# Doorbell_With_Power_Supply.net
KiCad netlist of a schematic drawn in EAGLE
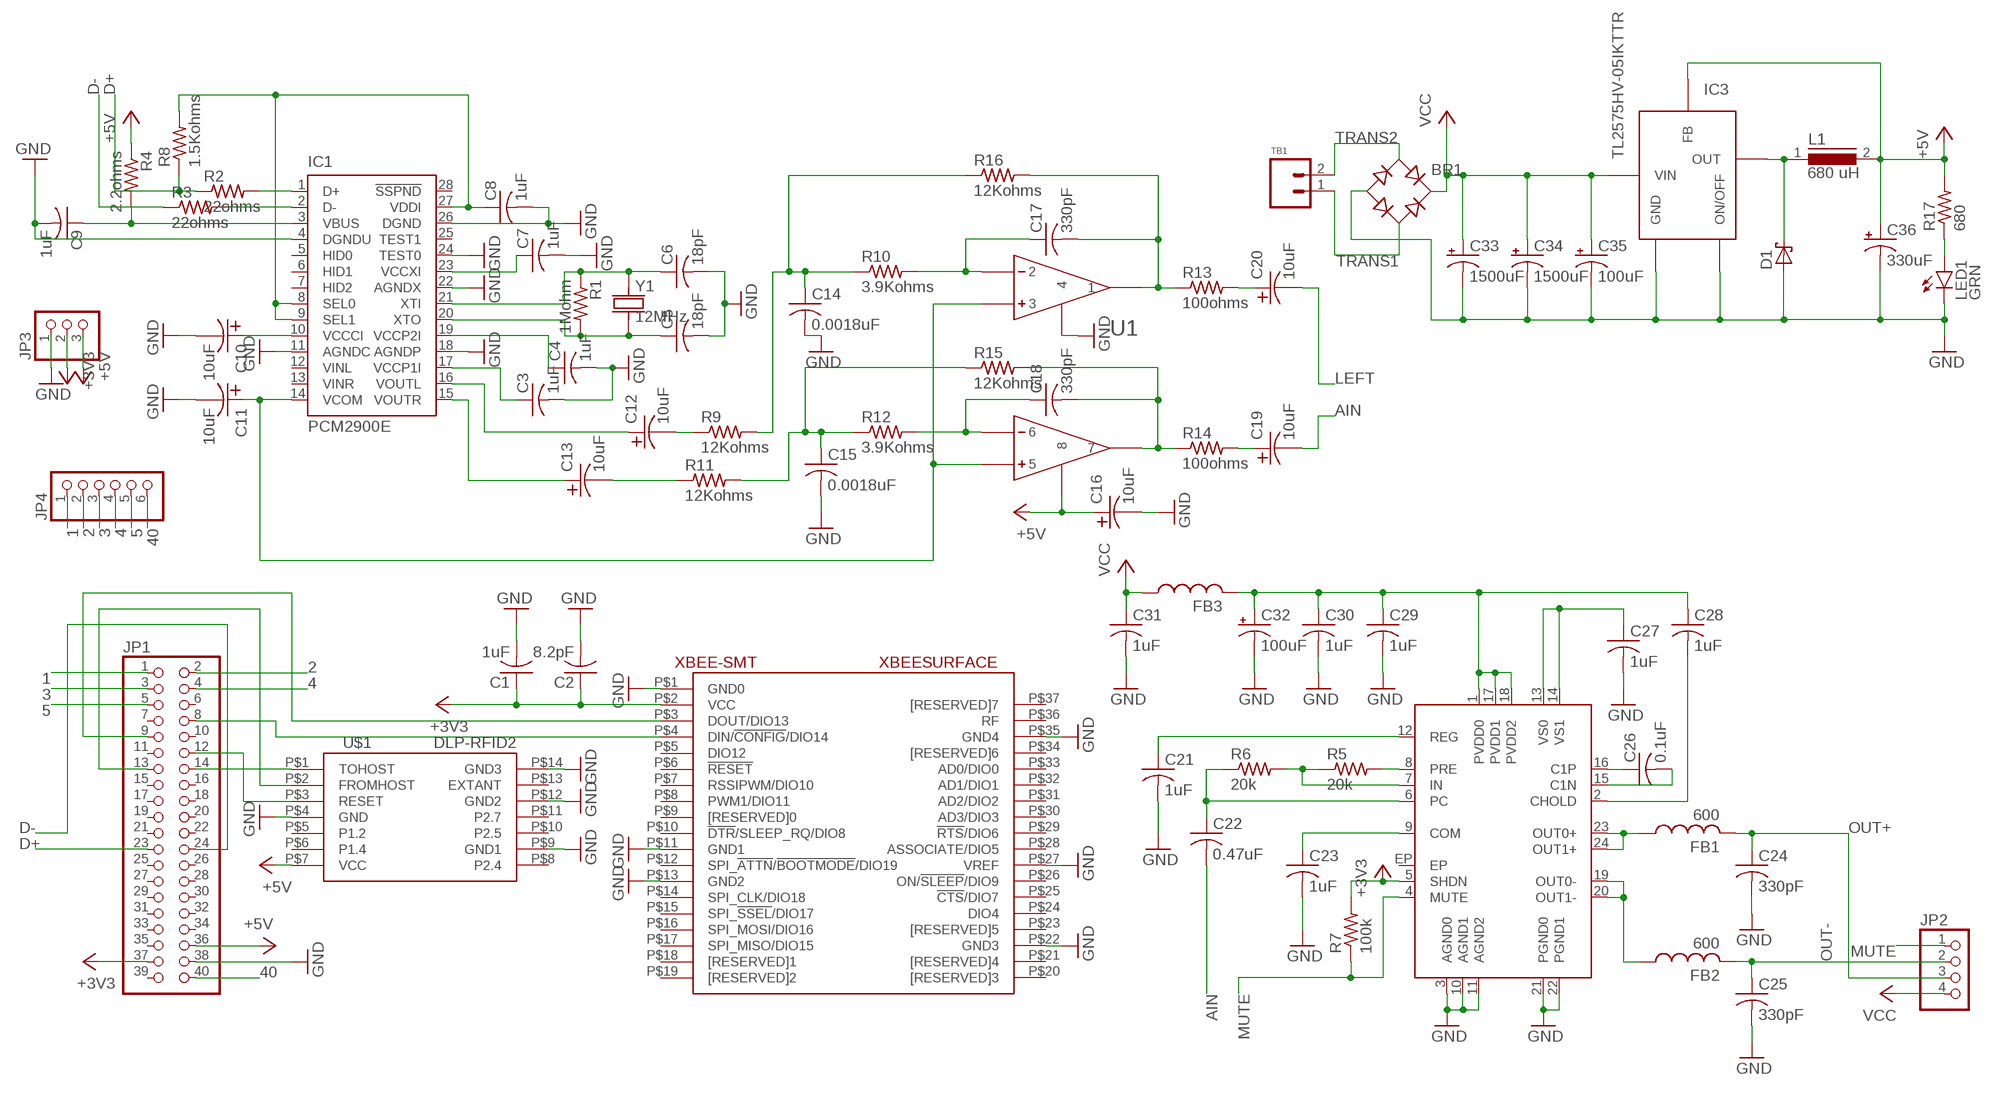
[diagram p0: schematic, sheet 1]

(export (version "E")
  (design (tool "Eeschema 10.0.6"))
  (components
    (comp (ref "BR1")
      (value "BR")
      (footprint "eagle-import:DFS")
      (fields (field (name "MANF") "Comchip Technology"))
      (libsource (lib "eagle-import") (part "BR"))
    )
    (comp (ref "C1")
      (value "1uF")
      (footprint "eagle-import:0603_CAP")
      (libsource (lib "eagle-import") (part "CAP0603"))
    )
    (comp (ref "C2")
      (value "8.2pF")
      (footprint "eagle-import:0603_CAP")
      (libsource (lib "eagle-import") (part "CAP0603"))
    )
    (comp (ref "C3")
      (value "1uF")
      (footprint "eagle-import:0603_CAP")
      (libsource (lib "eagle-import") (part "CAP0603"))
    )
    (comp (ref "C4")
      (value "1uF")
      (footprint "eagle-import:0603_CAP")
      (libsource (lib "eagle-import") (part "CAP0603"))
    )
    (comp (ref "C5")
      (value "18pF")
      (footprint "eagle-import:0603_CAP")
      (libsource (lib "eagle-import") (part "CAP0603"))
    )
    (comp (ref "C6")
      (value "18pF")
      (footprint "eagle-import:0603_CAP")
      (libsource (lib "eagle-import") (part "CAP0603"))
    )
    (comp (ref "C7")
      (value "1uF")
      (footprint "eagle-import:0603_CAP")
      (libsource (lib "eagle-import") (part "CAP0603"))
    )
    (comp (ref "C8")
      (value "1uF")
      (footprint "eagle-import:0603_CAP")
      (libsource (lib "eagle-import") (part "CAP0603"))
    )
    (comp (ref "C9")
      (value "1uF")
      (footprint "eagle-import:0603_CAP")
      (libsource (lib "eagle-import") (part "CAP0603"))
    )
    (comp (ref "C10")
      (value "10uF")
      (footprint "eagle-import:1411_CAP")
      (libsource (lib "eagle-import") (part "CAP-TANT"))
    )
    (comp (ref "C11")
      (value "10uF")
      (footprint "eagle-import:1411_CAP")
      (libsource (lib "eagle-import") (part "CAP-TANT"))
    )
    (comp (ref "C12")
      (value "10uF")
      (footprint "eagle-import:1411_CAP")
      (libsource (lib "eagle-import") (part "CAP-TANT"))
    )
    (comp (ref "C13")
      (value "10uF")
      (footprint "eagle-import:1411_CAP")
      (libsource (lib "eagle-import") (part "CAP-TANT"))
    )
    (comp (ref "C14")
      (value "0.0018uF")
      (footprint "eagle-import:0603_CAP")
      (libsource (lib "eagle-import") (part "CAP0603"))
    )
    (comp (ref "C15")
      (value "0.0018uF")
      (footprint "eagle-import:0603_CAP")
      (libsource (lib "eagle-import") (part "CAP0603"))
    )
    (comp (ref "C16")
      (value "10uF")
      (footprint "eagle-import:1411_CAP")
      (libsource (lib "eagle-import") (part "CAP-TANT"))
    )
    (comp (ref "C17")
      (value "330pF")
      (footprint "eagle-import:0603_CAP")
      (libsource (lib "eagle-import") (part "CAP0603"))
    )
    (comp (ref "C18")
      (value "330pF")
      (footprint "eagle-import:0603_CAP")
      (libsource (lib "eagle-import") (part "CAP0603"))
    )
    (comp (ref "C19")
      (value "10uF")
      (footprint "eagle-import:1411_CAP")
      (libsource (lib "eagle-import") (part "CAP-TANT"))
    )
    (comp (ref "C20")
      (value "10uF")
      (footprint "eagle-import:1411_CAP")
      (libsource (lib "eagle-import") (part "CAP-TANT"))
    )
    (comp (ref "C21")
      (value "1uF")
      (footprint "eagle-import:0603_CAP")
      (libsource (lib "eagle-import") (part "CAP0603"))
    )
    (comp (ref "C22")
      (value "0.47uF")
      (footprint "eagle-import:0603_CAP")
      (libsource (lib "eagle-import") (part "CAP0603"))
    )
    (comp (ref "C23")
      (value "1uF")
      (footprint "eagle-import:0603_CAP")
      (libsource (lib "eagle-import") (part "CAP0603"))
    )
    (comp (ref "C24")
      (value "330pF")
      (footprint "eagle-import:0603_CAP")
      (libsource (lib "eagle-import") (part "CAP0603"))
    )
    (comp (ref "C25")
      (value "330pF")
      (footprint "eagle-import:0603_CAP")
      (libsource (lib "eagle-import") (part "CAP0603"))
    )
    (comp (ref "C26")
      (value "0.1uF")
      (footprint "eagle-import:0603_CAP")
      (libsource (lib "eagle-import") (part "CAP0603"))
    )
    (comp (ref "C27")
      (value "1uF")
      (footprint "eagle-import:0603_CAP")
      (libsource (lib "eagle-import") (part "CAP0603"))
    )
    (comp (ref "C28")
      (value "1uF")
      (footprint "eagle-import:0603_CAP")
      (libsource (lib "eagle-import") (part "CAP0603"))
    )
    (comp (ref "C29")
      (value "1uF")
      (footprint "eagle-import:0603_CAP")
      (libsource (lib "eagle-import") (part "CAP0603"))
    )
    (comp (ref "C30")
      (value "1uF")
      (footprint "eagle-import:0603_CAP")
      (libsource (lib "eagle-import") (part "CAP0603"))
    )
    (comp (ref "C31")
      (value "1uF")
      (footprint "eagle-import:0603_CAP")
      (libsource (lib "eagle-import") (part "CAP0603"))
    )
    (comp (ref "C32")
      (value "100uF")
      (footprint "eagle-import:F_CAP")
      (libsource (lib "eagle-import") (part "CAP_POLF"))
    )
    (comp (ref "C33")
      (value "1500uF")
      (footprint "eagle-import:J16_CAP")
      (libsource (lib "eagle-import") (part "CAP_POLJ16"))
    )
    (comp (ref "C34")
      (value "1500uF")
      (footprint "eagle-import:J16_CAP")
      (libsource (lib "eagle-import") (part "CAP_POLJ16"))
    )
    (comp (ref "C35")
      (value "100uF")
      (footprint "eagle-import:F_CAP")
      (libsource (lib "eagle-import") (part "CAP_POLF"))
    )
    (comp (ref "C36")
      (value "330uF")
      (footprint "eagle-import:F_CAP")
      (libsource (lib "eagle-import") (part "CAP_POLF"))
    )
    (comp (ref "D1")
      (value "SCHOTTKY_DIODE")
      (footprint "eagle-import:SMD_DIODE")
      (fields (field (name "MANF") "Diodes Inc"))
      (libsource (lib "eagle-import") (part "SCHOTTKY_DIODE"))
    )
    (comp (ref "FB1")
      (value "600")
      (footprint "eagle-import:0805_FB")
      (libsource (lib "eagle-import") (part "FB0805"))
    )
    (comp (ref "FB2")
      (value "600")
      (footprint "eagle-import:0805_FB")
      (libsource (lib "eagle-import") (part "FB0805"))
    )
    (comp (ref "FB3")
      (value "FB0805")
      (footprint "eagle-import:0805_FB")
      (libsource (lib "eagle-import") (part "FB0805"))
    )
    (comp (ref "IC1")
      (value "PCM2900E")
      (footprint "eagle-import:SSOP28DB")
      (fields (field (name "MF") "TEXAS INSTRUMENTS"))
      (libsource (lib "eagle-import") (part "PCM2900E"))
    )
    (comp (ref "IC2")
      (value "MAX9737")
      (footprint "eagle-import:TQFN24")
      (fields (field (name "MANF") "Maxim"))
      (libsource (lib "eagle-import") (part "MAX9737"))
    )
    (comp (ref "IC3")
      (value "TL2575HV-05IKTTR")
      (footprint "eagle-import:TO-263-5")
      (fields (field (name "MANF") "Texas Instruments"))
      (libsource (lib "eagle-import") (part "TL2575"))
    )
    (comp (ref "JP1")
      (value "PINHD-2X20")
      (footprint "eagle-import:2X20")
      (libsource (lib "eagle-import") (part "PINHD-2X20"))
    )
    (comp (ref "JP2")
      (value "PINHD-1X4")
      (footprint "eagle-import:1X04")
      (libsource (lib "eagle-import") (part "PINHD-1X4"))
    )
    (comp (ref "JP3")
      (value "PINHD-1X3")
      (footprint "eagle-import:1X03")
      (libsource (lib "eagle-import") (part "PINHD-1X3"))
    )
    (comp (ref "JP4")
      (value "PINHD-1X6")
      (footprint "eagle-import:1X06")
      (libsource (lib "eagle-import") (part "PINHD-1X6"))
    )
    (comp (ref "L1")
      (value "680 uH")
      (footprint "eagle-import:DR125")
      (fields (field (name "MANF") "Bourns Inc."))
      (libsource (lib "eagle-import") (part "DR125"))
    )
    (comp (ref "LED1")
      (value "GRN")
      (footprint "eagle-import:0603_LED")
      (fields (field (name "MANF") "Avago Technologies"))
      (libsource (lib "eagle-import") (part "LED0603"))
    )
    (comp (ref "R1")
      (value "1Mohm")
      (footprint "eagle-import:0603_RESISTOR")
      (libsource (lib "eagle-import") (part "RESISTOR0603"))
    )
    (comp (ref "R2")
      (value "22ohms")
      (footprint "eagle-import:0603_RESISTOR")
      (libsource (lib "eagle-import") (part "RESISTOR0603"))
    )
    (comp (ref "R3")
      (value "22ohms")
      (footprint "eagle-import:0603_RESISTOR")
      (libsource (lib "eagle-import") (part "RESISTOR0603"))
    )
    (comp (ref "R4")
      (value "2.2ohms")
      (footprint "eagle-import:0603_RESISTOR")
      (libsource (lib "eagle-import") (part "RESISTOR0603"))
    )
    (comp (ref "R5")
      (value "20k")
      (footprint "eagle-import:0603_RESISTOR")
      (libsource (lib "eagle-import") (part "RESISTOR0603"))
    )
    (comp (ref "R6")
      (value "20k")
      (footprint "eagle-import:0603_RESISTOR")
      (libsource (lib "eagle-import") (part "RESISTOR0603"))
    )
    (comp (ref "R7")
      (value "100k")
      (footprint "eagle-import:0603_RESISTOR")
      (libsource (lib "eagle-import") (part "RESISTOR0603"))
    )
    (comp (ref "R8")
      (value "1.5Kohms")
      (footprint "eagle-import:0603_RESISTOR")
      (libsource (lib "eagle-import") (part "RESISTOR0603"))
    )
    (comp (ref "R9")
      (value "12Kohms")
      (footprint "eagle-import:0603_RESISTOR")
      (libsource (lib "eagle-import") (part "RESISTOR0603"))
    )
    (comp (ref "R10")
      (value "3.9Kohms")
      (footprint "eagle-import:0603_RESISTOR")
      (libsource (lib "eagle-import") (part "RESISTOR0603"))
    )
    (comp (ref "R11")
      (value "12Kohms")
      (footprint "eagle-import:0603_RESISTOR")
      (libsource (lib "eagle-import") (part "RESISTOR0603"))
    )
    (comp (ref "R12")
      (value "3.9Kohms")
      (footprint "eagle-import:0603_RESISTOR")
      (libsource (lib "eagle-import") (part "RESISTOR0603"))
    )
    (comp (ref "R13")
      (value "100ohms")
      (footprint "eagle-import:0603_RESISTOR")
      (libsource (lib "eagle-import") (part "RESISTOR0603"))
    )
    (comp (ref "R14")
      (value "100ohms")
      (footprint "eagle-import:0603_RESISTOR")
      (libsource (lib "eagle-import") (part "RESISTOR0603"))
    )
    (comp (ref "R15")
      (value "12Kohms")
      (footprint "eagle-import:0603_RESISTOR")
      (libsource (lib "eagle-import") (part "RESISTOR0603"))
    )
    (comp (ref "R16")
      (value "12Kohms")
      (footprint "eagle-import:0603_RESISTOR")
      (libsource (lib "eagle-import") (part "RESISTOR0603"))
    )
    (comp (ref "R17")
      (value "680")
      (footprint "eagle-import:0603_RESISTOR")
      (libsource (lib "eagle-import") (part "RESISTOR0603"))
    )
    (comp (ref "TB1")
      (value "TERMINAL_BLOCK_2")
      (footprint "eagle-import:TERMINAL_BLOCK_2")
      (fields (field (name "MANF") "Phoenix"))
      (libsource (lib "eagle-import") (part "TERMINAL_BLOCK_2"))
    )
    (comp (ref "U$1")
      (value "DLP-RFID2")
      (footprint "eagle-import:DLP-RFID2")
      (libsource (lib "eagle-import") (part "DLP-RFID2"))
    )
    (comp (ref "U1")
      (value "OP-AMP")
      (footprint "eagle-import:OPA2353UA")
      (libsource (lib "eagle-import") (part "OP-AMP"))
    )
    (comp (ref "XBEE-SMT")
      (value "XBEESURFACE")
      (footprint "eagle-import:XBEESURFACE")
      (libsource (lib "eagle-import") (part "XBEESURFACE"))
    )
    (comp (ref "Y1")
      (value "12MHz")
      (footprint "eagle-import:CRYSTAL_5X3")
      (libsource (lib "eagle-import") (part "CRYSTAL5X3"))
    )
  )
  (nets
    (net (code "1") (name "+3V3") (class "Default")
      (node (ref "C1") (pin "1") (pinfunction "1_1") (pintype "passive"))
      (node (ref "C2") (pin "1") (pinfunction "1_1") (pintype "passive"))
      (node (ref "IC2") (pin "5") (pinfunction "SHDN_5") (pintype "input"))
      (node (ref "JP1") (pin "37") (pinfunction "37_37") (pintype "passive"))
      (node (ref "JP3") (pin "2") (pinfunction "2_2") (pintype "passive"))
      (node (ref "R7") (pin "2") (pinfunction "2_2") (pintype "passive"))
      (node (ref "XBEE-SMT") (pin "P$2") (pinfunction "VCC_P$2") (pintype "bidirectional"))
    )
    (net (code "2") (name "+5V") (class "Default")
      (node (ref "C16") (pin "P$1") (pinfunction "P$1_P$1") (pintype "passive"))
      (node (ref "C36") (pin "+") (pinfunction "+_+") (pintype "passive"))
      (node (ref "IC3") (pin "4") (pinfunction "FB_4") (pintype "input"))
      (node (ref "JP1") (pin "36") (pinfunction "36_36") (pintype "passive"))
      (node (ref "JP3") (pin "3") (pinfunction "3_3") (pintype "passive"))
      (node (ref "L1") (pin "2") (pinfunction "2_2") (pintype "passive"))
      (node (ref "R17") (pin "2") (pinfunction "2_2") (pintype "passive"))
      (node (ref "R4") (pin "1") (pinfunction "1_1") (pintype "passive"))
      (node (ref "U$1") (pin "P$7") (pinfunction "VCC_P$7") (pintype "bidirectional"))
      (node (ref "U1") (pin "P$8") (pinfunction "8_P$8") (pintype "bidirectional"))
    )
    (net (code "3") (name "/1") (class "Default")
      (node (ref "JP1") (pin "1") (pinfunction "1_1") (pintype "passive"))
      (node (ref "JP4") (pin "1") (pinfunction "1_1") (pintype "passive"))
    )
    (net (code "4") (name "/2") (class "Default")
      (node (ref "JP1") (pin "2") (pinfunction "2_2") (pintype "passive"))
      (node (ref "JP4") (pin "2") (pinfunction "2_2") (pintype "passive"))
    )
    (net (code "5") (name "/3") (class "Default")
      (node (ref "JP1") (pin "3") (pinfunction "3_3") (pintype "passive"))
      (node (ref "JP4") (pin "3") (pinfunction "3_3") (pintype "passive"))
    )
    (net (code "6") (name "/4") (class "Default")
      (node (ref "JP1") (pin "4") (pinfunction "4_4") (pintype "passive"))
      (node (ref "JP4") (pin "4") (pinfunction "4_4") (pintype "passive"))
    )
    (net (code "7") (name "/5") (class "Default")
      (node (ref "JP1") (pin "5") (pinfunction "5_5") (pintype "passive"))
      (node (ref "JP4") (pin "5") (pinfunction "5_5") (pintype "passive"))
    )
    (net (code "8") (name "/40") (class "Default")
      (node (ref "JP1") (pin "40") (pinfunction "40_40") (pintype "passive"))
      (node (ref "JP4") (pin "6") (pinfunction "6_6") (pintype "passive"))
    )
    (net (code "9") (name "/AIN") (class "Default")
      (node (ref "C19") (pin "P$2") (pinfunction "P$2_P$2") (pintype "passive"))
      (node (ref "C22") (pin "2") (pinfunction "2_2") (pintype "passive"))
    )
    (net (code "10") (name "/D+") (class "Default")
      (node (ref "JP1") (pin "23") (pinfunction "23_23") (pintype "passive"))
      (node (ref "R2") (pin "1") (pinfunction "1_1") (pintype "passive"))
      (node (ref "R8") (pin "1") (pinfunction "1_1") (pintype "passive"))
    )
    (net (code "11") (name "/D-") (class "Default")
      (node (ref "JP1") (pin "24") (pinfunction "24_24") (pintype "passive"))
      (node (ref "R3") (pin "1") (pinfunction "1_1") (pintype "passive"))
    )
    (net (code "12") (name "/LEFT") (class "Default")
      (node (ref "C20") (pin "P$2") (pinfunction "P$2_P$2") (pintype "passive"))
    )
    (net (code "13") (name "/MUTE") (class "Default")
      (node (ref "IC2") (pin "4") (pinfunction "MUTE_4") (pintype "input"))
      (node (ref "JP2") (pin "1") (pinfunction "1_1") (pintype "passive"))
      (node (ref "R7") (pin "1") (pinfunction "1_1") (pintype "passive"))
    )
    (net (code "14") (name "/OUT+") (class "Default")
      (node (ref "C24") (pin "1") (pinfunction "1_1") (pintype "passive"))
      (node (ref "FB1") (pin "2") (pinfunction "2_2") (pintype "passive"))
      (node (ref "JP2") (pin "3") (pinfunction "3_3") (pintype "passive"))
    )
    (net (code "15") (name "/OUT-") (class "Default")
      (node (ref "C25") (pin "1") (pinfunction "1_1") (pintype "passive"))
      (node (ref "FB2") (pin "2") (pinfunction "2_2") (pintype "passive"))
      (node (ref "JP2") (pin "2") (pinfunction "2_2") (pintype "passive"))
    )
    (net (code "16") (name "/TRANS1") (class "Default")
      (node (ref "BR1") (pin "AC2") (pinfunction "AC2_AC2") (pintype "passive"))
      (node (ref "TB1") (pin "1") (pinfunction "1_1") (pintype "passive"))
    )
    (net (code "17") (name "/TRANS2") (class "Default")
      (node (ref "BR1") (pin "AC1") (pinfunction "AC1_AC1") (pintype "passive"))
      (node (ref "TB1") (pin "2") (pinfunction "2_2") (pintype "passive"))
    )
    (net (code "18") (name "GND") (class "Default")
      (node (ref "BR1") (pin "-") (pinfunction "-_-") (pintype "passive"))
      (node (ref "C1") (pin "2") (pinfunction "2_2") (pintype "passive"))
      (node (ref "C10") (pin "P$2") (pinfunction "P$2_P$2") (pintype "passive"))
      (node (ref "C11") (pin "P$2") (pinfunction "P$2_P$2") (pintype "passive"))
      (node (ref "C14") (pin "2") (pinfunction "2_2") (pintype "passive"))
      (node (ref "C15") (pin "2") (pinfunction "2_2") (pintype "passive"))
      (node (ref "C16") (pin "P$2") (pinfunction "P$2_P$2") (pintype "passive"))
      (node (ref "C2") (pin "2") (pinfunction "2_2") (pintype "passive"))
      (node (ref "C21") (pin "2") (pinfunction "2_2") (pintype "passive"))
      (node (ref "C23") (pin "2") (pinfunction "2_2") (pintype "passive"))
      (node (ref "C24") (pin "2") (pinfunction "2_2") (pintype "passive"))
      (node (ref "C25") (pin "2") (pinfunction "2_2") (pintype "passive"))
      (node (ref "C27") (pin "2") (pinfunction "2_2") (pintype "passive"))
      (node (ref "C29") (pin "2") (pinfunction "2_2") (pintype "passive"))
      (node (ref "C3") (pin "2") (pinfunction "2_2") (pintype "passive"))
      (node (ref "C30") (pin "2") (pinfunction "2_2") (pintype "passive"))
      (node (ref "C31") (pin "2") (pinfunction "2_2") (pintype "passive"))
      (node (ref "C32") (pin "-") (pinfunction "-_-") (pintype "passive"))
      (node (ref "C33") (pin "-") (pinfunction "-_-") (pintype "passive"))
      (node (ref "C34") (pin "-") (pinfunction "-_-") (pintype "passive"))
      (node (ref "C35") (pin "-") (pinfunction "-_-") (pintype "passive"))
      (node (ref "C36") (pin "-") (pinfunction "-_-") (pintype "passive"))
      (node (ref "C4") (pin "2") (pinfunction "2_2") (pintype "passive"))
      (node (ref "C5") (pin "2") (pinfunction "2_2") (pintype "passive"))
      (node (ref "C6") (pin "2") (pinfunction "2_2") (pintype "passive"))
      (node (ref "C7") (pin "2") (pinfunction "2_2") (pintype "passive"))
      (node (ref "C8") (pin "2") (pinfunction "2_2") (pintype "passive"))
      (node (ref "C9") (pin "2") (pinfunction "2_2") (pintype "passive"))
      (node (ref "D1") (pin "A") (pinfunction "A_A") (pintype "passive"))
      (node (ref "IC1") (pin "11") (pinfunction "AGNDC_11") (pintype "power_in"))
      (node (ref "IC1") (pin "18") (pinfunction "AGNDP_18") (pintype "power_in"))
      (node (ref "IC1") (pin "22") (pinfunction "AGNDX_22") (pintype "power_in"))
      (node (ref "IC1") (pin "24") (pinfunction "TEST0_24") (pintype "input"))
      (node (ref "IC1") (pin "26") (pinfunction "DGND_26") (pintype "power_in"))
      (node (ref "IC1") (pin "4") (pinfunction "DGNDU_4") (pintype "power_in"))
      (node (ref "IC2") (pin "10") (pinfunction "AGND1_10") (pintype "power_in"))
      (node (ref "IC2") (pin "11") (pinfunction "AGND2_11") (pintype "power_in"))
      (node (ref "IC2") (pin "21") (pinfunction "PGND0_21") (pintype "power_in"))
      (node (ref "IC2") (pin "22") (pinfunction "PGND1_22") (pintype "power_in"))
      (node (ref "IC2") (pin "3") (pinfunction "AGND0_3") (pintype "power_in"))
      (node (ref "IC3") (pin "3") (pinfunction "GND_3") (pintype "power_in"))
      (node (ref "IC3") (pin "5") (pinfunction "ON/OFF_5") (pintype "input"))
      (node (ref "JP1") (pin "38") (pinfunction "38_38") (pintype "passive"))
      (node (ref "JP3") (pin "1") (pinfunction "1_1") (pintype "passive"))
      (node (ref "LED1") (pin "C") (pinfunction "C_C") (pintype "passive"))
      (node (ref "U$1") (pin "P$12") (pinfunction "GND2_P$12") (pintype "bidirectional"))
      (node (ref "U$1") (pin "P$14") (pinfunction "GND3_P$14") (pintype "bidirectional"))
      (node (ref "U$1") (pin "P$4") (pinfunction "GND_P$4") (pintype "bidirectional"))
      (node (ref "U$1") (pin "P$9") (pinfunction "GND1_P$9") (pintype "bidirectional"))
      (node (ref "U1") (pin "P$4") (pinfunction "4_P$4") (pintype "bidirectional"))
      (node (ref "XBEE-SMT") (pin "P$1") (pinfunction "GND0_P$1") (pintype "bidirectional"))
      (node (ref "XBEE-SMT") (pin "P$11") (pinfunction "GND1_P$11") (pintype "bidirectional"))
      (node (ref "XBEE-SMT") (pin "P$13") (pinfunction "GND2_P$13") (pintype "bidirectional"))
      (node (ref "XBEE-SMT") (pin "P$22") (pinfunction "GND3_P$22") (pintype "bidirectional"))
      (node (ref "XBEE-SMT") (pin "P$27") (pinfunction "VREF_P$27") (pintype "bidirectional"))
      (node (ref "XBEE-SMT") (pin "P$35") (pinfunction "GND4_P$35") (pintype "bidirectional"))
    )
    (net (code "19") (name "Net-(C12-PadP$2)") (class "Default")
      (node (ref "C12") (pin "P$2") (pinfunction "P$2_P$2") (pintype "passive"))
      (node (ref "R9") (pin "1") (pinfunction "1_1") (pintype "passive"))
    )
    (net (code "20") (name "Net-(C13-PadP$2)") (class "Default")
      (node (ref "C13") (pin "P$2") (pinfunction "P$2_P$2") (pintype "passive"))
      (node (ref "R11") (pin "1") (pinfunction "1_1") (pintype "passive"))
    )
    (net (code "21") (name "Net-(C14-Pad1)") (class "Default")
      (node (ref "C14") (pin "1") (pinfunction "1_1") (pintype "passive"))
      (node (ref "R10") (pin "1") (pinfunction "1_1") (pintype "passive"))
      (node (ref "R16") (pin "1") (pinfunction "1_1") (pintype "passive"))
      (node (ref "R9") (pin "2") (pinfunction "2_2") (pintype "passive"))
    )
    (net (code "22") (name "Net-(C15-Pad1)") (class "Default")
      (node (ref "C15") (pin "1") (pinfunction "1_1") (pintype "passive"))
      (node (ref "R11") (pin "2") (pinfunction "2_2") (pintype "passive"))
      (node (ref "R12") (pin "1") (pinfunction "1_1") (pintype "passive"))
      (node (ref "R15") (pin "1") (pinfunction "1_1") (pintype "passive"))
    )
    (net (code "23") (name "Net-(C19-PadP$1)") (class "Default")
      (node (ref "C19") (pin "P$1") (pinfunction "P$1_P$1") (pintype "passive"))
      (node (ref "R14") (pin "2") (pinfunction "2_2") (pintype "passive"))
    )
    (net (code "24") (name "Net-(C20-PadP$1)") (class "Default")
      (node (ref "C20") (pin "P$1") (pinfunction "P$1_P$1") (pintype "passive"))
      (node (ref "R13") (pin "2") (pinfunction "2_2") (pintype "passive"))
    )
    (net (code "25") (name "Net-(IC1-D+)") (class "Default")
      (node (ref "IC1") (pin "1") (pinfunction "D+_1") (pintype "bidirectional"))
      (node (ref "R2") (pin "2") (pinfunction "2_2") (pintype "passive"))
    )
    (net (code "26") (name "Net-(IC1-D-)") (class "Default")
      (node (ref "IC1") (pin "2") (pinfunction "D-_2") (pintype "bidirectional"))
      (node (ref "R3") (pin "2") (pinfunction "2_2") (pintype "passive"))
    )
    (net (code "27") (name "Net-(IC1-SEL0)") (class "Default")
      (node (ref "C8") (pin "1") (pinfunction "1_1") (pintype "passive"))
      (node (ref "IC1") (pin "27") (pinfunction "VDDI_27") (pintype "power_in"))
      (node (ref "IC1") (pin "8") (pinfunction "SEL0_8") (pintype "input"))
      (node (ref "IC1") (pin "9") (pinfunction "SEL1_9") (pintype "input"))
      (node (ref "R8") (pin "2") (pinfunction "2_2") (pintype "passive"))
    )
    (net (code "28") (name "Net-(IC1-VBUS)") (class "Default")
      (node (ref "C9") (pin "1") (pinfunction "1_1") (pintype "passive"))
      (node (ref "IC1") (pin "3") (pinfunction "VBUS_3") (pintype "power_in"))
      (node (ref "R4") (pin "2") (pinfunction "2_2") (pintype "passive"))
    )
    (net (code "29") (name "Net-(IC1-VCCCI)") (class "Default")
      (node (ref "C10") (pin "P$1") (pinfunction "P$1_P$1") (pintype "passive"))
      (node (ref "IC1") (pin "10") (pinfunction "VCCCI_10") (pintype "power_in"))
    )
    (net (code "30") (name "Net-(IC1-VCCP1I)") (class "Default")
      (node (ref "C3") (pin "1") (pinfunction "1_1") (pintype "passive"))
      (node (ref "IC1") (pin "17") (pinfunction "VCCP1I_17") (pintype "input"))
    )
    (net (code "31") (name "Net-(IC1-VCCP2I)") (class "Default")
      (node (ref "C4") (pin "1") (pinfunction "1_1") (pintype "passive"))
      (node (ref "IC1") (pin "19") (pinfunction "VCCP2I_19") (pintype "power_in"))
    )
    (net (code "32") (name "Net-(IC1-VCCXI)") (class "Default")
      (node (ref "C7") (pin "1") (pinfunction "1_1") (pintype "passive"))
      (node (ref "IC1") (pin "23") (pinfunction "VCCXI_23") (pintype "power_in"))
    )
    (net (code "33") (name "Net-(IC1-VCOM)") (class "Default")
      (node (ref "C11") (pin "P$1") (pinfunction "P$1_P$1") (pintype "passive"))
      (node (ref "IC1") (pin "14") (pinfunction "VCOM_14") (pintype "power_in"))
      (node (ref "U1") (pin "P$3") (pinfunction "3_P$3") (pintype "bidirectional"))
      (node (ref "U1") (pin "P$5") (pinfunction "5_P$5") (pintype "bidirectional"))
    )
    (net (code "34") (name "Net-(IC1-VOUTL)") (class "Default")
      (node (ref "C12") (pin "P$1") (pinfunction "P$1_P$1") (pintype "passive"))
      (node (ref "IC1") (pin "16") (pinfunction "VOUTL_16") (pintype "output"))
    )
    (net (code "35") (name "Net-(IC1-VOUTR)") (class "Default")
      (node (ref "C13") (pin "P$1") (pinfunction "P$1_P$1") (pintype "passive"))
      (node (ref "IC1") (pin "15") (pinfunction "VOUTR_15") (pintype "output"))
    )
    (net (code "36") (name "Net-(IC1-XTI)") (class "Default")
      (node (ref "C6") (pin "1") (pinfunction "1_1") (pintype "passive"))
      (node (ref "IC1") (pin "21") (pinfunction "XTI_21") (pintype "input"))
      (node (ref "R1") (pin "1") (pinfunction "1_1") (pintype "passive"))
      (node (ref "Y1") (pin "1") (pinfunction "1_1") (pintype "passive"))
    )
    (net (code "37") (name "Net-(IC1-XTO)") (class "Default")
      (node (ref "C5") (pin "1") (pinfunction "1_1") (pintype "passive"))
      (node (ref "IC1") (pin "20") (pinfunction "XTO_20") (pintype "output"))
      (node (ref "R1") (pin "2") (pinfunction "2_2") (pintype "passive"))
      (node (ref "Y1") (pin "2") (pinfunction "2_2") (pintype "passive"))
    )
    (net (code "38") (name "Net-(IC2-C1N)") (class "Default")
      (node (ref "C26") (pin "2") (pinfunction "2_2") (pintype "passive"))
      (node (ref "IC2") (pin "15") (pinfunction "C1N_15") (pintype "output"))
    )
    (net (code "39") (name "Net-(IC2-C1P)") (class "Default")
      (node (ref "C26") (pin "1") (pinfunction "1_1") (pintype "passive"))
      (node (ref "IC2") (pin "16") (pinfunction "C1P_16") (pintype "output"))
    )
    (net (code "40") (name "Net-(IC2-CHOLD)") (class "Default")
      (node (ref "C28") (pin "2") (pinfunction "2_2") (pintype "passive"))
      (node (ref "IC2") (pin "2") (pinfunction "CHOLD_2") (pintype "output"))
    )
    (net (code "41") (name "Net-(IC2-COM)") (class "Default")
      (node (ref "C23") (pin "1") (pinfunction "1_1") (pintype "passive"))
      (node (ref "IC2") (pin "9") (pinfunction "COM_9") (pintype "input"))
    )
    (net (code "42") (name "Net-(IC2-IN)") (class "Default")
      (node (ref "IC2") (pin "7") (pinfunction "IN_7") (pintype "input"))
      (node (ref "R5") (pin "1") (pinfunction "1_1") (pintype "passive"))
      (node (ref "R6") (pin "2") (pinfunction "2_2") (pintype "passive"))
    )
    (net (code "43") (name "Net-(IC2-OUT0+)") (class "Default")
      (node (ref "FB1") (pin "1") (pinfunction "1_1") (pintype "passive"))
      (node (ref "IC2") (pin "23") (pinfunction "OUT0+_23") (pintype "output"))
      (node (ref "IC2") (pin "24") (pinfunction "OUT1+_24") (pintype "output"))
    )
    (net (code "44") (name "Net-(IC2-OUT0-)") (class "Default")
      (node (ref "FB2") (pin "1") (pinfunction "1_1") (pintype "passive"))
      (node (ref "IC2") (pin "19") (pinfunction "OUT0-_19") (pintype "output"))
      (node (ref "IC2") (pin "20") (pinfunction "OUT1-_20") (pintype "output"))
    )
    (net (code "45") (name "Net-(IC2-PC)") (class "Default")
      (node (ref "C22") (pin "1") (pinfunction "1_1") (pintype "passive"))
      (node (ref "IC2") (pin "6") (pinfunction "PC_6") (pintype "input"))
      (node (ref "R6") (pin "1") (pinfunction "1_1") (pintype "passive"))
    )
    (net (code "46") (name "Net-(IC2-PRE)") (class "Default")
      (node (ref "IC2") (pin "8") (pinfunction "PRE_8") (pintype "output"))
      (node (ref "R5") (pin "2") (pinfunction "2_2") (pintype "passive"))
    )
    (net (code "47") (name "Net-(IC2-PVDD0)") (class "Default")
      (node (ref "C28") (pin "1") (pinfunction "1_1") (pintype "passive"))
      (node (ref "C29") (pin "1") (pinfunction "1_1") (pintype "passive"))
      (node (ref "C30") (pin "1") (pinfunction "1_1") (pintype "passive"))
      (node (ref "C32") (pin "+") (pinfunction "+_+") (pintype "passive"))
      (node (ref "FB3") (pin "2") (pinfunction "2_2") (pintype "passive"))
      (node (ref "IC2") (pin "1") (pinfunction "PVDD0_1") (pintype "power_in"))
      (node (ref "IC2") (pin "17") (pinfunction "PVDD1_17") (pintype "power_in"))
      (node (ref "IC2") (pin "18") (pinfunction "PVDD2_18") (pintype "power_in"))
    )
    (net (code "48") (name "Net-(IC2-REG)") (class "Default")
      (node (ref "C21") (pin "1") (pinfunction "1_1") (pintype "passive"))
      (node (ref "IC2") (pin "12") (pinfunction "REG_12") (pintype "output"))
    )
    (net (code "49") (name "Net-(IC2-VS0)") (class "Default")
      (node (ref "C27") (pin "1") (pinfunction "1_1") (pintype "passive"))
      (node (ref "IC2") (pin "13") (pinfunction "VS0_13") (pintype "output"))
      (node (ref "IC2") (pin "14") (pinfunction "VS1_14") (pintype "output"))
    )
    (net (code "50") (name "Net-(IC3-OUT)") (class "Default")
      (node (ref "D1") (pin "C") (pinfunction "C_C") (pintype "passive"))
      (node (ref "IC3") (pin "2") (pinfunction "OUT_2") (pintype "power_in"))
      (node (ref "L1") (pin "1") (pinfunction "1_1") (pintype "passive"))
    )
    (net (code "51") (name "Net-(LED1-PadA)") (class "Default")
      (node (ref "LED1") (pin "A") (pinfunction "A_A") (pintype "passive"))
      (node (ref "R17") (pin "1") (pinfunction "1_1") (pintype "passive"))
    )
    (net (code "52") (name "Net-(U$1-FROMHOST)") (class "Default")
      (node (ref "JP1") (pin "13") (pinfunction "13_13") (pintype "passive"))
      (node (ref "U$1") (pin "P$2") (pinfunction "FROMHOST_P$2") (pintype "bidirectional"))
    )
    (net (code "53") (name "Net-(U$1-RESET)") (class "Default")
      (node (ref "JP1") (pin "12") (pinfunction "12_12") (pintype "passive"))
      (node (ref "U$1") (pin "P$3") (pinfunction "RESET_P$3") (pintype "bidirectional"))
    )
    (net (code "54") (name "Net-(U$1-TOHOST)") (class "Default")
      (node (ref "JP1") (pin "14") (pinfunction "14_14") (pintype "passive"))
      (node (ref "U$1") (pin "P$1") (pinfunction "TOHOST_P$1") (pintype "bidirectional"))
    )
    (net (code "55") (name "Net-(U1-1)") (class "Default")
      (node (ref "C17") (pin "2") (pinfunction "2_2") (pintype "passive"))
      (node (ref "R13") (pin "1") (pinfunction "1_1") (pintype "passive"))
      (node (ref "R16") (pin "2") (pinfunction "2_2") (pintype "passive"))
      (node (ref "U1") (pin "P$1") (pinfunction "1_P$1") (pintype "bidirectional"))
    )
    (net (code "56") (name "Net-(U1-2)") (class "Default")
      (node (ref "C17") (pin "1") (pinfunction "1_1") (pintype "passive"))
      (node (ref "R10") (pin "2") (pinfunction "2_2") (pintype "passive"))
      (node (ref "U1") (pin "P$2") (pinfunction "2_P$2") (pintype "bidirectional"))
    )
    (net (code "57") (name "Net-(U1-6)") (class "Default")
      (node (ref "C18") (pin "1") (pinfunction "1_1") (pintype "passive"))
      (node (ref "R12") (pin "2") (pinfunction "2_2") (pintype "passive"))
      (node (ref "U1") (pin "P$6") (pinfunction "6_P$6") (pintype "bidirectional"))
    )
    (net (code "58") (name "Net-(U1-7)") (class "Default")
      (node (ref "C18") (pin "2") (pinfunction "2_2") (pintype "passive"))
      (node (ref "R14") (pin "1") (pinfunction "1_1") (pintype "passive"))
      (node (ref "R15") (pin "2") (pinfunction "2_2") (pintype "passive"))
      (node (ref "U1") (pin "P$7") (pinfunction "7_P$7") (pintype "bidirectional"))
    )
    (net (code "59") (name "Net-(XBEE-SMT-DIN{slash}~{CONFIG}{slash}DIO14)") (class "Default")
      (node (ref "JP1") (pin "8") (pinfunction "8_8") (pintype "passive"))
      (node (ref "XBEE-SMT") (pin "P$4") (pinfunction "DIN/~{CONFIG}/DIO14_P$4") (pintype "bidirectional"))
    )
    (net (code "60") (name "Net-(XBEE-SMT-DOUT{slash}DIO13)") (class "Default")
      (node (ref "JP1") (pin "9") (pinfunction "9_9") (pintype "passive"))
      (node (ref "XBEE-SMT") (pin "P$3") (pinfunction "DOUT/DIO13_P$3") (pintype "bidirectional"))
    )
    (net (code "61") (name "VCC") (class "Default")
      (node (ref "BR1") (pin "+") (pinfunction "+_+") (pintype "passive"))
      (node (ref "C31") (pin "1") (pinfunction "1_1") (pintype "passive"))
      (node (ref "C33") (pin "+") (pinfunction "+_+") (pintype "passive"))
      (node (ref "C34") (pin "+") (pinfunction "+_+") (pintype "passive"))
      (node (ref "C35") (pin "+") (pinfunction "+_+") (pintype "passive"))
      (node (ref "FB3") (pin "1") (pinfunction "1_1") (pintype "passive"))
      (node (ref "IC3") (pin "1") (pinfunction "VIN_1") (pintype "power_in"))
      (node (ref "JP2") (pin "4") (pinfunction "4_4") (pintype "passive"))
    )
    (net (code "62") (name "unconnected-(IC1-HID0-Pad5)") (class "Default")
      (node (ref "IC1") (pin "5") (pinfunction "HID0_5") (pintype "input"))
    )
    (net (code "63") (name "unconnected-(IC1-HID1-Pad6)") (class "Default")
      (node (ref "IC1") (pin "6") (pinfunction "HID1_6") (pintype "input"))
    )
    (net (code "64") (name "unconnected-(IC1-HID2-Pad7)") (class "Default")
      (node (ref "IC1") (pin "7") (pinfunction "HID2_7") (pintype "input"))
    )
    (net (code "65") (name "unconnected-(IC1-TEST1-Pad25)") (class "Default")
      (node (ref "IC1") (pin "25") (pinfunction "TEST1_25") (pintype "output"))
    )
    (net (code "66") (name "unconnected-(IC1-VINL-Pad12)") (class "Default")
      (node (ref "IC1") (pin "12") (pinfunction "VINL_12") (pintype "input"))
    )
    (net (code "67") (name "unconnected-(IC1-VINR-Pad13)") (class "Default")
      (node (ref "IC1") (pin "13") (pinfunction "VINR_13") (pintype "input"))
    )
    (net (code "68") (name "unconnected-(IC1-~{SSPND}-Pad28)") (class "Default")
      (node (ref "IC1") (pin "28") (pinfunction "~{SSPND}_28") (pintype "output"))
    )
    (net (code "69") (name "unconnected-(IC2-PadEP)") (class "Default")
      (node (ref "IC2") (pin "EP") (pinfunction "EP_EP") (pintype "passive"))
    )
    (net (code "70") (name "unconnected-(JP1-Pad6)") (class "Default")
      (node (ref "JP1") (pin "6") (pinfunction "6_6") (pintype "passive"))
    )
    (net (code "71") (name "unconnected-(JP1-Pad7)") (class "Default")
      (node (ref "JP1") (pin "7") (pinfunction "7_7") (pintype "passive"))
    )
    (net (code "72") (name "unconnected-(JP1-Pad10)") (class "Default")
      (node (ref "JP1") (pin "10") (pinfunction "10_10") (pintype "passive"))
    )
    (net (code "73") (name "unconnected-(JP1-Pad11)") (class "Default")
      (node (ref "JP1") (pin "11") (pinfunction "11_11") (pintype "passive"))
    )
    (net (code "74") (name "unconnected-(JP1-Pad15)") (class "Default")
      (node (ref "JP1") (pin "15") (pinfunction "15_15") (pintype "passive"))
    )
    (net (code "75") (name "unconnected-(JP1-Pad16)") (class "Default")
      (node (ref "JP1") (pin "16") (pinfunction "16_16") (pintype "passive"))
    )
    (net (code "76") (name "unconnected-(JP1-Pad17)") (class "Default")
      (node (ref "JP1") (pin "17") (pinfunction "17_17") (pintype "passive"))
    )
    (net (code "77") (name "unconnected-(JP1-Pad18)") (class "Default")
      (node (ref "JP1") (pin "18") (pinfunction "18_18") (pintype "passive"))
    )
    (net (code "78") (name "unconnected-(JP1-Pad19)") (class "Default")
      (node (ref "JP1") (pin "19") (pinfunction "19_19") (pintype "passive"))
    )
    (net (code "79") (name "unconnected-(JP1-Pad20)") (class "Default")
      (node (ref "JP1") (pin "20") (pinfunction "20_20") (pintype "passive"))
    )
    (net (code "80") (name "unconnected-(JP1-Pad21)") (class "Default")
      (node (ref "JP1") (pin "21") (pinfunction "21_21") (pintype "passive"))
    )
    (net (code "81") (name "unconnected-(JP1-Pad22)") (class "Default")
      (node (ref "JP1") (pin "22") (pinfunction "22_22") (pintype "passive"))
    )
    (net (code "82") (name "unconnected-(JP1-Pad25)") (class "Default")
      (node (ref "JP1") (pin "25") (pinfunction "25_25") (pintype "passive"))
    )
    (net (code "83") (name "unconnected-(JP1-Pad26)") (class "Default")
      (node (ref "JP1") (pin "26") (pinfunction "26_26") (pintype "passive"))
    )
    (net (code "84") (name "unconnected-(JP1-Pad27)") (class "Default")
      (node (ref "JP1") (pin "27") (pinfunction "27_27") (pintype "passive"))
    )
    (net (code "85") (name "unconnected-(JP1-Pad28)") (class "Default")
      (node (ref "JP1") (pin "28") (pinfunction "28_28") (pintype "passive"))
    )
    (net (code "86") (name "unconnected-(JP1-Pad29)") (class "Default")
      (node (ref "JP1") (pin "29") (pinfunction "29_29") (pintype "passive"))
    )
    (net (code "87") (name "unconnected-(JP1-Pad30)") (class "Default")
      (node (ref "JP1") (pin "30") (pinfunction "30_30") (pintype "passive"))
    )
    (net (code "88") (name "unconnected-(JP1-Pad31)") (class "Default")
      (node (ref "JP1") (pin "31") (pinfunction "31_31") (pintype "passive"))
    )
    (net (code "89") (name "unconnected-(JP1-Pad32)") (class "Default")
      (node (ref "JP1") (pin "32") (pinfunction "32_32") (pintype "passive"))
    )
    (net (code "90") (name "unconnected-(JP1-Pad33)") (class "Default")
      (node (ref "JP1") (pin "33") (pinfunction "33_33") (pintype "passive"))
    )
    (net (code "91") (name "unconnected-(JP1-Pad34)") (class "Default")
      (node (ref "JP1") (pin "34") (pinfunction "34_34") (pintype "passive"))
    )
    (net (code "92") (name "unconnected-(JP1-Pad35)") (class "Default")
      (node (ref "JP1") (pin "35") (pinfunction "35_35") (pintype "passive"))
    )
    (net (code "93") (name "unconnected-(JP1-Pad39)") (class "Default")
      (node (ref "JP1") (pin "39") (pinfunction "39_39") (pintype "passive"))
    )
    (net (code "94") (name "unconnected-(U$1-EXTANT-PadP$13)") (class "Default")
      (node (ref "U$1") (pin "P$13") (pinfunction "EXTANT_P$13") (pintype "bidirectional"))
    )
    (net (code "95") (name "unconnected-(U$1-P1.2-PadP$5)") (class "Default")
      (node (ref "U$1") (pin "P$5") (pinfunction "P1.2_P$5") (pintype "bidirectional"))
    )
    (net (code "96") (name "unconnected-(U$1-P1.4-PadP$6)") (class "Default")
      (node (ref "U$1") (pin "P$6") (pinfunction "P1.4_P$6") (pintype "bidirectional"))
    )
    (net (code "97") (name "unconnected-(U$1-P2.4-PadP$8)") (class "Default")
      (node (ref "U$1") (pin "P$8") (pinfunction "P2.4_P$8") (pintype "bidirectional"))
    )
    (net (code "98") (name "unconnected-(U$1-P2.5-PadP$10)") (class "Default")
      (node (ref "U$1") (pin "P$10") (pinfunction "P2.5_P$10") (pintype "bidirectional"))
    )
    (net (code "99") (name "unconnected-(U$1-P2.7-PadP$11)") (class "Default")
      (node (ref "U$1") (pin "P$11") (pinfunction "P2.7_P$11") (pintype "bidirectional"))
    )
    (net (code "100") (name "unconnected-(XBEE-SMT-AD0{slash}DIO0-PadP$33)") (class "Default")
      (node (ref "XBEE-SMT") (pin "P$33") (pinfunction "AD0/DIO0_P$33") (pintype "bidirectional"))
    )
    (net (code "101") (name "unconnected-(XBEE-SMT-AD1{slash}DIO1-PadP$32)") (class "Default")
      (node (ref "XBEE-SMT") (pin "P$32") (pinfunction "AD1/DIO1_P$32") (pintype "bidirectional"))
    )
    (net (code "102") (name "unconnected-(XBEE-SMT-AD2{slash}DIO2-PadP$31)") (class "Default")
      (node (ref "XBEE-SMT") (pin "P$31") (pinfunction "AD2/DIO2_P$31") (pintype "bidirectional"))
    )
    (net (code "103") (name "unconnected-(XBEE-SMT-AD3{slash}DIO3-PadP$30)") (class "Default")
      (node (ref "XBEE-SMT") (pin "P$30") (pinfunction "AD3/DIO3_P$30") (pintype "bidirectional"))
    )
    (net (code "104") (name "unconnected-(XBEE-SMT-ASSOCIATE{slash}DIO5-PadP$28)") (class "Default")
      (node (ref "XBEE-SMT") (pin "P$28") (pinfunction "ASSOCIATE/DIO5_P$28") (pintype "bidirectional"))
    )
    (net (code "105") (name "unconnected-(XBEE-SMT-DIO4-PadP$24)") (class "Default")
      (node (ref "XBEE-SMT") (pin "P$24") (pinfunction "DIO4_P$24") (pintype "bidirectional"))
    )
    (net (code "106") (name "unconnected-(XBEE-SMT-DIO12-PadP$5)") (class "Default")
      (node (ref "XBEE-SMT") (pin "P$5") (pinfunction "DIO12_P$5") (pintype "bidirectional"))
    )
    (net (code "107") (name "unconnected-(XBEE-SMT-ON{slash}~{SLEEP}{slash}DIO9-PadP$26)") (class "Default")
      (node (ref "XBEE-SMT") (pin "P$26") (pinfunction "ON/~{SLEEP}/DIO9_P$26") (pintype "bidirectional"))
    )
    (net (code "108") (name "unconnected-(XBEE-SMT-PWM1{slash}DIO11-PadP$8)") (class "Default")
      (node (ref "XBEE-SMT") (pin "P$8") (pinfunction "PWM1/DIO11_P$8") (pintype "bidirectional"))
    )
    (net (code "109") (name "unconnected-(XBEE-SMT-RF-PadP$36)") (class "Default")
      (node (ref "XBEE-SMT") (pin "P$36") (pinfunction "RF_P$36") (pintype "bidirectional"))
    )
    (net (code "110") (name "unconnected-(XBEE-SMT-RSSIPWM{slash}DIO10-PadP$7)") (class "Default")
      (node (ref "XBEE-SMT") (pin "P$7") (pinfunction "RSSIPWM/DIO10_P$7") (pintype "bidirectional"))
    )
    (net (code "111") (name "unconnected-(XBEE-SMT-SPI_CLK{slash}DIO18-PadP$14)") (class "Default")
      (node (ref "XBEE-SMT") (pin "P$14") (pinfunction "SPI_CLK/DIO18_P$14") (pintype "bidirectional"))
    )
    (net (code "112") (name "unconnected-(XBEE-SMT-SPI_MISO{slash}DIO15-PadP$17)") (class "Default")
      (node (ref "XBEE-SMT") (pin "P$17") (pinfunction "SPI_MISO/DIO15_P$17") (pintype "bidirectional"))
    )
    (net (code "113") (name "unconnected-(XBEE-SMT-SPI_MOSI{slash}DIO16-PadP$16)") (class "Default")
      (node (ref "XBEE-SMT") (pin "P$16") (pinfunction "SPI_MOSI/DIO16_P$16") (pintype "bidirectional"))
    )
    (net (code "114") (name "unconnected-(XBEE-SMT-SPI_~{ATTN}{slash}~{BOOTMODE}{slash}DIO19-PadP$12)") (class "Default")
      (node (ref "XBEE-SMT") (pin "P$12") (pinfunction "SPI_~{ATTN}/~{BOOTMODE}/DIO19_P$12") (pintype "bidirectional"))
    )
    (net (code "115") (name "unconnected-(XBEE-SMT-SPI_~{SSEL}{slash}DIO17-PadP$15)") (class "Default")
      (node (ref "XBEE-SMT") (pin "P$15") (pinfunction "SPI_~{SSEL}/DIO17_P$15") (pintype "bidirectional"))
    )
    (net (code "116") (name "unconnected-(XBEE-SMT-[RESERVED]0-PadP$9)") (class "Default")
      (node (ref "XBEE-SMT") (pin "P$9") (pinfunction "[RESERVED]0_P$9") (pintype "bidirectional"))
    )
    (net (code "117") (name "unconnected-(XBEE-SMT-[RESERVED]1-PadP$18)") (class "Default")
      (node (ref "XBEE-SMT") (pin "P$18") (pinfunction "[RESERVED]1_P$18") (pintype "bidirectional"))
    )
    (net (code "118") (name "unconnected-(XBEE-SMT-[RESERVED]2-PadP$19)") (class "Default")
      (node (ref "XBEE-SMT") (pin "P$19") (pinfunction "[RESERVED]2_P$19") (pintype "bidirectional"))
    )
    (net (code "119") (name "unconnected-(XBEE-SMT-[RESERVED]3-PadP$20)") (class "Default")
      (node (ref "XBEE-SMT") (pin "P$20") (pinfunction "[RESERVED]3_P$20") (pintype "bidirectional"))
    )
    (net (code "120") (name "unconnected-(XBEE-SMT-[RESERVED]4-PadP$21)") (class "Default")
      (node (ref "XBEE-SMT") (pin "P$21") (pinfunction "[RESERVED]4_P$21") (pintype "bidirectional"))
    )
    (net (code "121") (name "unconnected-(XBEE-SMT-[RESERVED]5-PadP$23)") (class "Default")
      (node (ref "XBEE-SMT") (pin "P$23") (pinfunction "[RESERVED]5_P$23") (pintype "bidirectional"))
    )
    (net (code "122") (name "unconnected-(XBEE-SMT-[RESERVED]6-PadP$34)") (class "Default")
      (node (ref "XBEE-SMT") (pin "P$34") (pinfunction "[RESERVED]6_P$34") (pintype "bidirectional"))
    )
    (net (code "123") (name "unconnected-(XBEE-SMT-[RESERVED]7-PadP$37)") (class "Default")
      (node (ref "XBEE-SMT") (pin "P$37") (pinfunction "[RESERVED]7_P$37") (pintype "bidirectional"))
    )
    (net (code "124") (name "unconnected-(XBEE-SMT-~{CTS}{slash}DIO7-PadP$25)") (class "Default")
      (node (ref "XBEE-SMT") (pin "P$25") (pinfunction "~{CTS}/DIO7_P$25") (pintype "bidirectional"))
    )
    (net (code "125") (name "unconnected-(XBEE-SMT-~{DTR}{slash}SLEEP_RQ{slash}DIO8-PadP$10)") (class "Default")
      (node (ref "XBEE-SMT") (pin "P$10") (pinfunction "~{DTR}/SLEEP_RQ/DIO8_P$10") (pintype "bidirectional"))
    )
    (net (code "126") (name "unconnected-(XBEE-SMT-~{RESET}-PadP$6)") (class "Default")
      (node (ref "XBEE-SMT") (pin "P$6") (pinfunction "~{RESET}_P$6") (pintype "bidirectional"))
    )
    (net (code "127") (name "unconnected-(XBEE-SMT-~{RTS}{slash}DIO6-PadP$29)") (class "Default")
      (node (ref "XBEE-SMT") (pin "P$29") (pinfunction "~{RTS}/DIO6_P$29") (pintype "bidirectional"))
    )
  )
)
